# 1602.net
KiCad netlist of a schematic drawn in Altium Designer
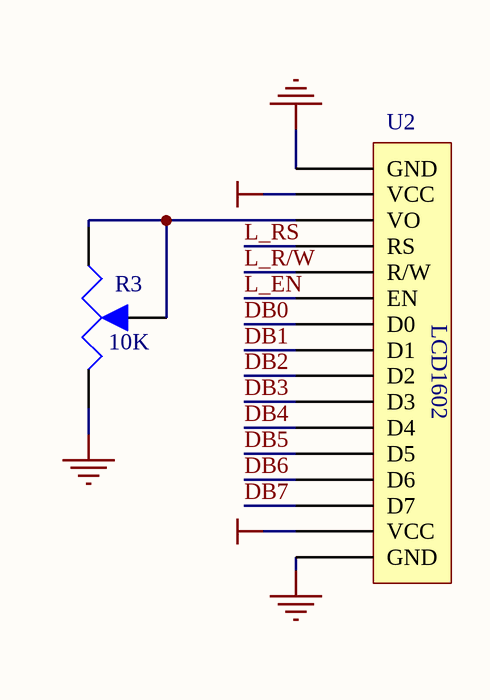
[diagram p0: 1602各引脚接线图.SCHDOC]

(export (version "E")
  (design (tool "Eeschema 10.0.6"))
  (components
    (comp (ref "R3")
      (value "10K")
      (footprint "3296")
      (fields (field (name "Comment") "Variable Resistor"))
      (libsource (lib "l_lib") (part "Variable Resistor"))
    )
    (comp (ref "U2") (value "LCD160") (footprint "LCD1602") (libsource (lib "l_lib") (part "LCD1602")))
  )
  (nets
    (net (code "1") (name "+5V") (class "Default")
      (node (ref "U2") (pin "15") (pinfunction "VCC_15") (pintype "power_in"))
      (node (ref "U2") (pin "2") (pinfunction "VCC_2") (pintype "power_in"))
    )
    (net (code "2") (name "/DB0") (class "Default")
      (node (ref "U2") (pin "7") (pinfunction "D0_7") (pintype "passive"))
    )
    (net (code "3") (name "/DB1") (class "Default")
      (node (ref "U2") (pin "8") (pinfunction "D1_8") (pintype "passive"))
    )
    (net (code "4") (name "/DB2") (class "Default")
      (node (ref "U2") (pin "9") (pinfunction "D2_9") (pintype "passive"))
    )
    (net (code "5") (name "/DB3") (class "Default")
      (node (ref "U2") (pin "10") (pinfunction "D3_10") (pintype "passive"))
    )
    (net (code "6") (name "/DB4") (class "Default")
      (node (ref "U2") (pin "11") (pinfunction "D4_11") (pintype "passive"))
    )
    (net (code "7") (name "/DB5") (class "Default")
      (node (ref "U2") (pin "12") (pinfunction "D5_12") (pintype "passive"))
    )
    (net (code "8") (name "/DB6") (class "Default")
      (node (ref "U2") (pin "13") (pinfunction "D6_13") (pintype "passive"))
    )
    (net (code "9") (name "/DB7") (class "Default")
      (node (ref "U2") (pin "14") (pinfunction "D7_14") (pintype "passive"))
    )
    (net (code "10") (name "/L_EN") (class "Default")
      (node (ref "U2") (pin "6") (pinfunction "EN_6") (pintype "passive"))
    )
    (net (code "11") (name "/L_RS") (class "Default")
      (node (ref "U2") (pin "4") (pinfunction "RS_4") (pintype "passive"))
    )
    (net (code "12") (name "/L_R{slash}W") (class "Default")
      (node (ref "U2") (pin "5") (pinfunction "R/W_5") (pintype "passive"))
    )
    (net (code "13") (name "GND") (class "Default")
      (node (ref "R3") (pin "2") (pinfunction "2_2") (pintype "passive"))
      (node (ref "U2") (pin "1") (pinfunction "GND_1") (pintype "power_in"))
      (node (ref "U2") (pin "16") (pinfunction "GND_16") (pintype "power_in"))
    )
    (net (code "14") (name "Net-(U2-VO)") (class "Default")
      (node (ref "R3") (pin "0") (pinfunction "0_0") (pintype "passive"))
      (node (ref "R3") (pin "1") (pinfunction "1_1") (pintype "passive"))
      (node (ref "U2") (pin "3") (pinfunction "VO_3") (pintype "passive"))
    )
  )
)
